# DiffAmp_K-0_2.net
KiCad netlist of a schematic drawn in Altium Designer
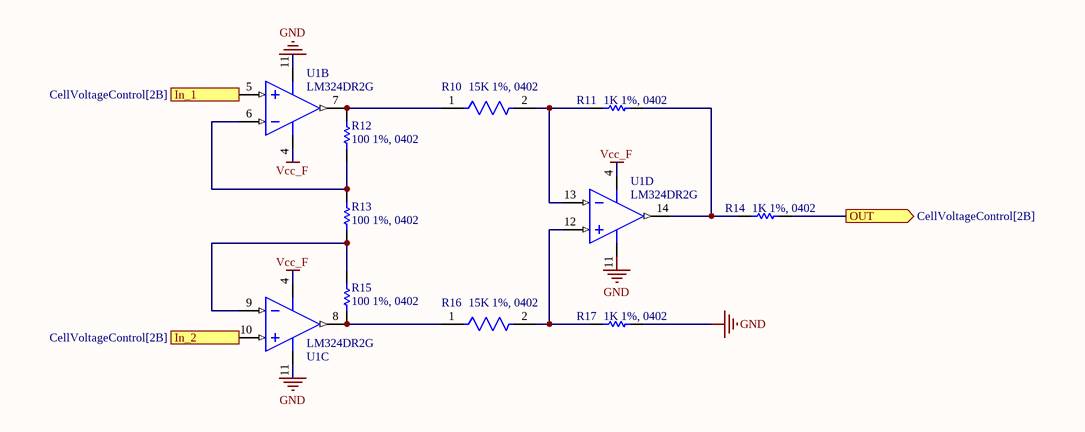
[diagram p0: DiffAmp_K-0.2.SchDoc]

(export (version "E")
  (design (tool "Eeschema 10.0.6"))
  (components
    (comp (ref "R10")
      (value "15K 1%, 0402")
      (footprint "FP-ERJ2R-MFG")
      (description "RES SMD 15K OHM 1% 1/10W 0402")
      (fields (field (name "TOLERANCE") "1%") (field (name "MANUFACTURER PART NUMBER") "ERJ-2RKF1502X"))
      (libsource (lib "Altium Content Vault") (part "1029c3af85768c4190bb7ad29bc67b5"))
    )
    (comp (ref "R11")
      (value "1K 1%, 0402")
      (footprint "RESC1005X40X25NL05T05")
      (description "Chip Resistor, 1 KOhm, +/- 1%, 100 mW, -55 to 155 degC, 0402 (1005 Metric), RoHS, Tape and Reel")
      (fields (field (name "PARTNUMBER") "ERJ-2RKF1001X") (field (name "MANUFACTURER") "Basic Passives"))
      (libsource (lib "Altium Content Vault") (part "RES-2"))
    )
    (comp (ref "R12")
      (value "100 1%, 0402")
      (footprint "RESC1005X40X25LL05T05")
      (description "Chip Resistor, 100 Ohm, +/- 1%, 100 mW, -55 to 155 degC, 0402 (1005 Metric), RoHS, Tape and Reel")
      (fields (field (name "MANUFACTURER") "Basic Passives") (field (name "TOLERANCE") "1%"))
      (libsource (lib "Altium Content Vault") (part "RES-2"))
    )
    (comp (ref "R13")
      (value "100 1%, 0402")
      (footprint "RESC1005X40X25LL05T05")
      (description "Chip Resistor, 100 Ohm, +/- 1%, 100 mW, -55 to 155 degC, 0402 (1005 Metric), RoHS, Tape and Reel")
      (fields (field (name "MANUFACTURER") "Basic Passives") (field (name "TOLERANCE") "1%"))
      (libsource (lib "Altium Content Vault") (part "RES-2"))
    )
    (comp (ref "R14")
      (value "1K 1%, 0402")
      (footprint "RESC1005X40X25NL05T05")
      (description "Chip Resistor, 1 KOhm, +/- 1%, 100 mW, -55 to 155 degC, 0402 (1005 Metric), RoHS, Tape and Reel")
      (fields (field (name "PARTNUMBER") "ERJ-2RKF1001X") (field (name "MANUFACTURER") "Basic Passives"))
      (libsource (lib "Altium Content Vault") (part "RES-2"))
    )
    (comp (ref "R15")
      (value "100 1%, 0402")
      (footprint "RESC1005X40X25LL05T05")
      (description "Chip Resistor, 100 Ohm, +/- 1%, 100 mW, -55 to 155 degC, 0402 (1005 Metric), RoHS, Tape and Reel")
      (fields (field (name "MANUFACTURER") "Basic Passives") (field (name "TOLERANCE") "1%"))
      (libsource (lib "Altium Content Vault") (part "RES-2"))
    )
    (comp (ref "R16")
      (value "15K 1%, 0402")
      (footprint "FP-ERJ2R-MFG")
      (description "RES SMD 15K OHM 1% 1/10W 0402")
      (fields (field (name "TOLERANCE") "1%") (field (name "MANUFACTURER PART NUMBER") "ERJ-2RKF1502X"))
      (libsource (lib "Altium Content Vault") (part "1029c3af85768c4190bb7ad29bc67b5"))
    )
    (comp (ref "R17")
      (value "1K 1%, 0402")
      (footprint "RESC1005X40X25NL05T05")
      (description "Chip Resistor, 1 KOhm, +/- 1%, 100 mW, -55 to 155 degC, 0402 (1005 Metric), RoHS, Tape and Reel")
      (fields (field (name "PARTNUMBER") "ERJ-2RKF1001X") (field (name "MANUFACTURER") "Basic Passives"))
      (libsource (lib "Altium Content Vault") (part "RES-2"))
    )
    (comp (ref "U1")
      (value "LM324DR2G")
      (footprint "ONSC-SOIC-14-751A-03_V")
      (fields (field (name "MANUFACTURER") "On Semiconductor"))
      (libsource (lib "Altium Content Vault") (part "ONSC-LM224_324_2902_NCV2902-14"))
    )
  )
  (nets
    (net (code "1") (name "/In_1") (class "Default")
      (node (ref "U1") (pin "5") (pinfunction "IN2+_5") (pintype "input"))
    )
    (net (code "2") (name "/In_2") (class "Default")
      (node (ref "U1") (pin "10") (pinfunction "IN3+_10") (pintype "input"))
    )
    (net (code "3") (name "/OUT") (class "Default")
      (node (ref "R14") (pin "2") (pinfunction "2_2") (pintype "passive"))
    )
    (net (code "4") (name "GND") (class "Default")
      (node (ref "R17") (pin "2") (pinfunction "2_2") (pintype "passive"))
      (node (ref "U1") (pin "11") (pinfunction "VEE/GND_11") (pintype "power_in"))
    )
    (net (code "5") (name "Net-(U1B-IN2-)") (class "Default")
      (node (ref "R12") (pin "1") (pinfunction "1_1") (pintype "passive"))
      (node (ref "R13") (pin "2") (pinfunction "2_2") (pintype "passive"))
      (node (ref "U1") (pin "6") (pinfunction "IN2-_6") (pintype "input"))
    )
    (net (code "6") (name "Net-(U1B-OUT2)") (class "Default")
      (node (ref "R10") (pin "1") (pinfunction "1_1") (pintype "passive"))
      (node (ref "R12") (pin "2") (pinfunction "2_2") (pintype "passive"))
      (node (ref "U1") (pin "7") (pinfunction "OUT2_7") (pintype "output"))
    )
    (net (code "7") (name "Net-(U1C-IN3-)") (class "Default")
      (node (ref "R13") (pin "1") (pinfunction "1_1") (pintype "passive"))
      (node (ref "R15") (pin "2") (pinfunction "2_2") (pintype "passive"))
      (node (ref "U1") (pin "9") (pinfunction "IN3-_9") (pintype "input"))
    )
    (net (code "8") (name "Net-(U1C-OUT3)") (class "Default")
      (node (ref "R15") (pin "1") (pinfunction "1_1") (pintype "passive"))
      (node (ref "R16") (pin "1") (pinfunction "1_1") (pintype "passive"))
      (node (ref "U1") (pin "8") (pinfunction "OUT3_8") (pintype "output"))
    )
    (net (code "9") (name "Net-(U1D-IN4+)") (class "Default")
      (node (ref "R16") (pin "2") (pinfunction "2_2") (pintype "passive"))
      (node (ref "R17") (pin "1") (pinfunction "1_1") (pintype "passive"))
      (node (ref "U1") (pin "12") (pinfunction "IN4+_12") (pintype "input"))
    )
    (net (code "10") (name "Net-(U1D-IN4-)") (class "Default")
      (node (ref "R10") (pin "2") (pinfunction "2_2") (pintype "passive"))
      (node (ref "R11") (pin "1") (pinfunction "1_1") (pintype "passive"))
      (node (ref "U1") (pin "13") (pinfunction "IN4-_13") (pintype "input"))
    )
    (net (code "11") (name "Net-(U1D-OUT4)") (class "Default")
      (node (ref "R11") (pin "2") (pinfunction "2_2") (pintype "passive"))
      (node (ref "R14") (pin "1") (pinfunction "1_1") (pintype "passive"))
      (node (ref "U1") (pin "14") (pinfunction "OUT4_14") (pintype "output"))
    )
    (net (code "12") (name "Vcc_F") (class "Default")
      (node (ref "U1") (pin "4") (pinfunction "VCC_4") (pintype "power_in"))
    )
    (net (code "13") (name "unconnected-(U1D-VEE{slash}GND-Pad11)") (class "Default")
      (node (ref "U1") (pin "11") (pinfunction "VEE/GND_11") (pintype "power_in"))
    )
  )
)
